# Analog_Teil_-_Kopie.net
KiCad netlist of a schematic drawn in EAGLE
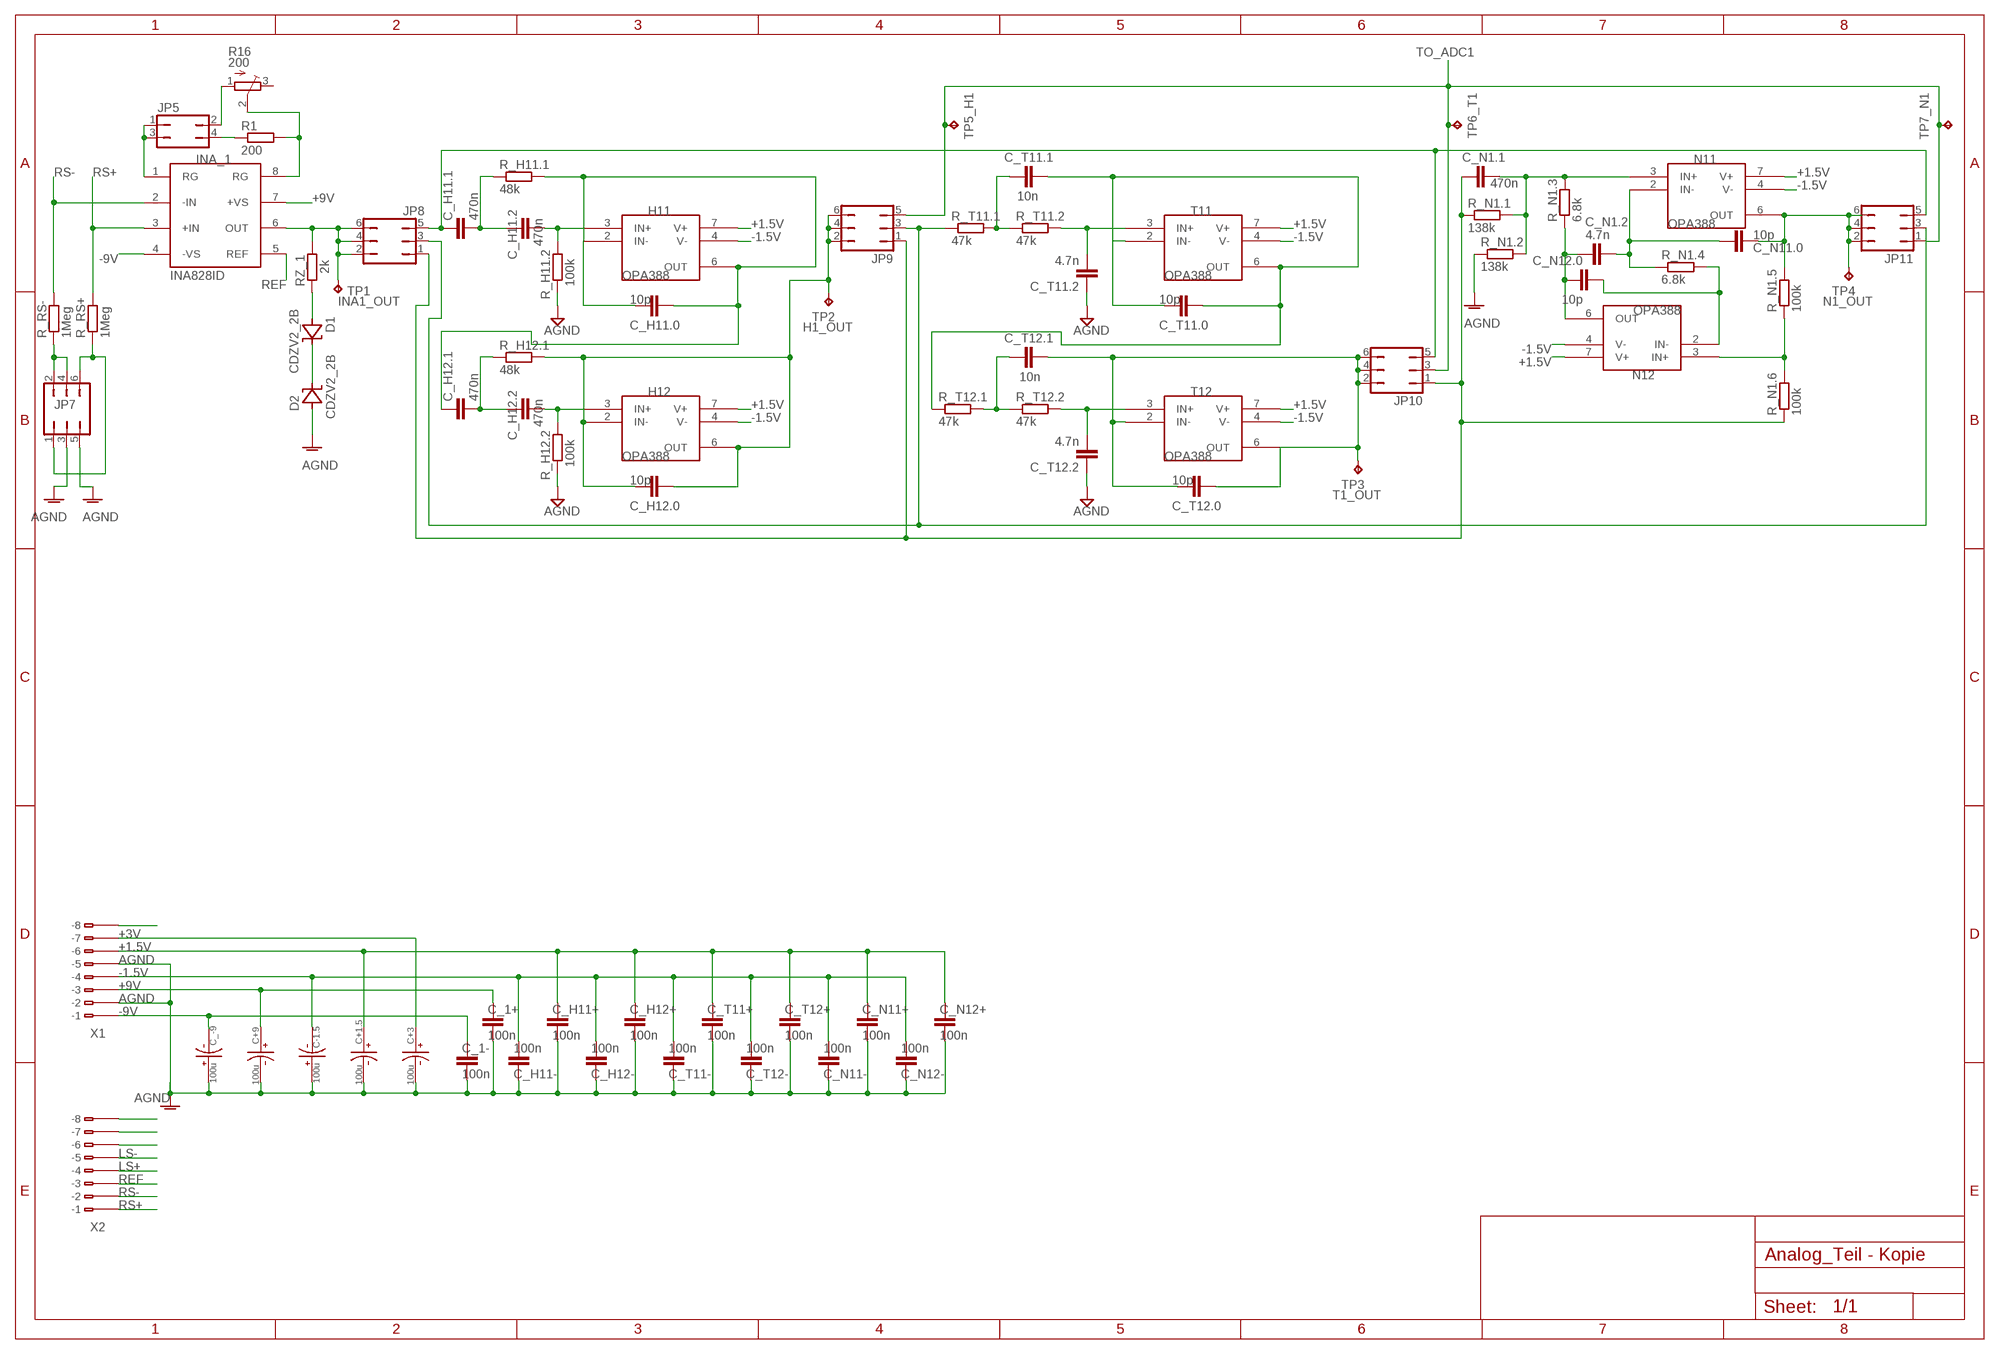
[diagram p0: schematic, sheet 1]

(export (version "E")
  (design (tool "Eeschema 10.0.6"))
  (components
    (comp (ref "C+1.5")
      (value "100u")
      (footprint "eagle-import:CAPPRD350W60D800H1150B")
      (fields (field (name "MF") "Panasonic Electronic") (field (name "MP") "ECA1HM101"))
      (libsource (lib "eagle-import") (part "ECA-1HM101"))
    )
    (comp (ref "C+3")
      (value "100u")
      (footprint "eagle-import:CAPPRD350W60D800H1150B")
      (fields (field (name "MF") "Panasonic Electronic") (field (name "MP") "ECA1HM101"))
      (libsource (lib "eagle-import") (part "ECA-1HM101"))
    )
    (comp (ref "C+9")
      (value "100u")
      (footprint "eagle-import:CAPPRD350W60D800H1150B")
      (fields (field (name "MF") "Panasonic Electronic") (field (name "MP") "ECA1HM101"))
      (libsource (lib "eagle-import") (part "ECA-1HM101"))
    )
    (comp (ref "C-1.5")
      (value "100u")
      (footprint "eagle-import:CAPPRD350W60D800H1150B")
      (fields (field (name "MF") "Panasonic Electronic") (field (name "MP") "ECA1HM101"))
      (libsource (lib "eagle-import") (part "ECA-1HM101"))
    )
    (comp (ref "C_-9")
      (value "100u")
      (footprint "eagle-import:CAPPRD350W60D800H1150B")
      (fields (field (name "MF") "Panasonic Electronic") (field (name "MP") "ECA1HM101"))
      (libsource (lib "eagle-import") (part "ECA-1HM101"))
    )
    (comp (ref "C_1+")
      (value "100n")
      (footprint "eagle-import:C0805")
      (libsource (lib "eagle-import") (part "C-EUC0805"))
    )
    (comp (ref "C_1-")
      (value "100n")
      (footprint "eagle-import:C0805")
      (libsource (lib "eagle-import") (part "C-EUC0805"))
    )
    (comp (ref "C_H11+")
      (value "100n")
      (footprint "eagle-import:C0805")
      (libsource (lib "eagle-import") (part "C-EUC0805"))
    )
    (comp (ref "C_H11-")
      (value "100n")
      (footprint "eagle-import:C0805")
      (libsource (lib "eagle-import") (part "C-EUC0805"))
    )
    (comp (ref "C_H11.0")
      (value "10p")
      (footprint "eagle-import:C0805")
      (libsource (lib "eagle-import") (part "C-EUC0805"))
    )
    (comp (ref "C_H11.1")
      (value "470n")
      (footprint "eagle-import:C0805")
      (libsource (lib "eagle-import") (part "C-EUC0805"))
    )
    (comp (ref "C_H11.2")
      (value "470n")
      (footprint "eagle-import:C0805")
      (libsource (lib "eagle-import") (part "C-EUC0805"))
    )
    (comp (ref "C_H12+")
      (value "100n")
      (footprint "eagle-import:C0805")
      (libsource (lib "eagle-import") (part "C-EUC0805"))
    )
    (comp (ref "C_H12-")
      (value "100n")
      (footprint "eagle-import:C0805")
      (libsource (lib "eagle-import") (part "C-EUC0805"))
    )
    (comp (ref "C_H12.0")
      (value "10p")
      (footprint "eagle-import:C0805")
      (libsource (lib "eagle-import") (part "C-EUC0805"))
    )
    (comp (ref "C_H12.1")
      (value "470n")
      (footprint "eagle-import:C0805")
      (libsource (lib "eagle-import") (part "C-EUC0805"))
    )
    (comp (ref "C_H12.2")
      (value "470n")
      (footprint "eagle-import:C0805")
      (libsource (lib "eagle-import") (part "C-EUC0805"))
    )
    (comp (ref "C_N1.1")
      (value "470n")
      (footprint "eagle-import:C0805")
      (libsource (lib "eagle-import") (part "C-EUC0805"))
    )
    (comp (ref "C_N1.2")
      (value "4.7n")
      (footprint "eagle-import:C0805")
      (libsource (lib "eagle-import") (part "C-EUC0805"))
    )
    (comp (ref "C_N11+")
      (value "100n")
      (footprint "eagle-import:C0805")
      (libsource (lib "eagle-import") (part "C-EUC0805"))
    )
    (comp (ref "C_N11-")
      (value "100n")
      (footprint "eagle-import:C0805")
      (libsource (lib "eagle-import") (part "C-EUC0805"))
    )
    (comp (ref "C_N11.0")
      (value "10p")
      (footprint "eagle-import:C0805")
      (libsource (lib "eagle-import") (part "C-EUC0805"))
    )
    (comp (ref "C_N12+")
      (value "100n")
      (footprint "eagle-import:C0805")
      (libsource (lib "eagle-import") (part "C-EUC0805"))
    )
    (comp (ref "C_N12-")
      (value "100n")
      (footprint "eagle-import:C0805")
      (libsource (lib "eagle-import") (part "C-EUC0805"))
    )
    (comp (ref "C_N12.0")
      (value "10p")
      (footprint "eagle-import:C0805")
      (libsource (lib "eagle-import") (part "C-EUC0805"))
    )
    (comp (ref "C_T11+")
      (value "100n")
      (footprint "eagle-import:C0805")
      (libsource (lib "eagle-import") (part "C-EUC0805"))
    )
    (comp (ref "C_T11-")
      (value "100n")
      (footprint "eagle-import:C0805")
      (libsource (lib "eagle-import") (part "C-EUC0805"))
    )
    (comp (ref "C_T11.0")
      (value "10p")
      (footprint "eagle-import:C0805")
      (libsource (lib "eagle-import") (part "C-EUC0805"))
    )
    (comp (ref "C_T11.1")
      (value "10n")
      (footprint "eagle-import:C0805")
      (libsource (lib "eagle-import") (part "C-EUC0805"))
    )
    (comp (ref "C_T11.2")
      (value "4.7n")
      (footprint "eagle-import:C0805")
      (libsource (lib "eagle-import") (part "C-EUC0805"))
    )
    (comp (ref "C_T12+")
      (value "100n")
      (footprint "eagle-import:C0805")
      (libsource (lib "eagle-import") (part "C-EUC0805"))
    )
    (comp (ref "C_T12-")
      (value "100n")
      (footprint "eagle-import:C0805")
      (libsource (lib "eagle-import") (part "C-EUC0805"))
    )
    (comp (ref "C_T12.0")
      (value "10p")
      (footprint "eagle-import:C0805")
      (libsource (lib "eagle-import") (part "C-EUC0805"))
    )
    (comp (ref "C_T12.1")
      (value "10n")
      (footprint "eagle-import:C0805")
      (libsource (lib "eagle-import") (part "C-EUC0805"))
    )
    (comp (ref "C_T12.2")
      (value "4.7n")
      (footprint "eagle-import:C0805")
      (libsource (lib "eagle-import") (part "C-EUC0805"))
    )
    (comp (ref "D1")
      (value "CDZV2_2B")
      (footprint "eagle-import:SODFL1006X40N")
      (libsource (lib "eagle-import") (part "CDZV2_2BSOD923"))
    )
    (comp (ref "D2")
      (value "CDZV2_2B")
      (footprint "eagle-import:SODFL1006X40N")
      (libsource (lib "eagle-import") (part "CDZV2_2BSOD923"))
    )
    (comp (ref "H11")
      (value "OPA388")
      (footprint "eagle-import:SOIC127P600X175-8N")
      (libsource (lib "eagle-import") (part "OPA388"))
    )
    (comp (ref "H12")
      (value "OPA388")
      (footprint "eagle-import:SOIC127P600X175-8N")
      (libsource (lib "eagle-import") (part "OPA388"))
    )
    (comp (ref "INA_1")
      (value "INA828ID")
      (footprint "eagle-import:SOIC8")
      (fields (field (name "DIGI-KEY_PART_NUMBER") "296-47415-ND") (field (name "MF") "Texas Instruments"))
      (libsource (lib "eagle-import") (part "INA828ID"))
    )
    (comp (ref "JP5")
      (value "JP2Q")
      (footprint "eagle-import:JP2Q")
      (libsource (lib "eagle-import") (part "JP2Q"))
    )
    (comp (ref "JP7")
      (value "JP3Q")
      (footprint "eagle-import:JP3Q")
      (libsource (lib "eagle-import") (part "JP3Q"))
    )
    (comp (ref "JP8")
      (value "JP3Q")
      (footprint "eagle-import:JP3Q")
      (libsource (lib "eagle-import") (part "JP3Q"))
    )
    (comp (ref "JP9")
      (value "JP3Q")
      (footprint "eagle-import:JP3Q")
      (libsource (lib "eagle-import") (part "JP3Q"))
    )
    (comp (ref "JP10")
      (value "JP3Q")
      (footprint "eagle-import:JP3Q")
      (libsource (lib "eagle-import") (part "JP3Q"))
    )
    (comp (ref "JP11")
      (value "JP3Q")
      (footprint "eagle-import:JP3Q")
      (libsource (lib "eagle-import") (part "JP3Q"))
    )
    (comp (ref "N11")
      (value "OPA388")
      (footprint "eagle-import:SOIC127P600X175-8N")
      (libsource (lib "eagle-import") (part "OPA388"))
    )
    (comp (ref "N12")
      (value "OPA388")
      (footprint "eagle-import:SOIC127P600X175-8N")
      (libsource (lib "eagle-import") (part "OPA388"))
    )
    (comp (ref "R1")
      (value "200")
      (footprint "eagle-import:R0805")
      (libsource (lib "eagle-import") (part "R-EU_R0805"))
    )
    (comp (ref "R16")
      (value "200")
      (footprint "eagle-import:SM-42_43W")
      (fields (field (name "SPICEPREFIX") "J"))
      (libsource (lib "eagle-import") (part "TRIM_EU-SM-42/43W"))
    )
    (comp (ref "RZ_1")
      (value "2k")
      (footprint "eagle-import:R0805")
      (libsource (lib "eagle-import") (part "R-EU_R0805"))
    )
    (comp (ref "R_H11.1")
      (value "48k")
      (footprint "eagle-import:R0805")
      (libsource (lib "eagle-import") (part "R-EU_R0805"))
    )
    (comp (ref "R_H11.2")
      (value "100k")
      (footprint "eagle-import:R0805")
      (libsource (lib "eagle-import") (part "R-EU_R0805"))
    )
    (comp (ref "R_H12.1")
      (value "48k")
      (footprint "eagle-import:R0805")
      (libsource (lib "eagle-import") (part "R-EU_R0805"))
    )
    (comp (ref "R_H12.2")
      (value "100k")
      (footprint "eagle-import:R0805")
      (libsource (lib "eagle-import") (part "R-EU_R0805"))
    )
    (comp (ref "R_N1.1")
      (value "138k")
      (footprint "eagle-import:R0805")
      (libsource (lib "eagle-import") (part "R-EU_R0805"))
    )
    (comp (ref "R_N1.2")
      (value "138k")
      (footprint "eagle-import:R0805")
      (libsource (lib "eagle-import") (part "R-EU_R0805"))
    )
    (comp (ref "R_N1.3")
      (value "6.8k")
      (footprint "eagle-import:R0805")
      (libsource (lib "eagle-import") (part "R-EU_R0805"))
    )
    (comp (ref "R_N1.4")
      (value "6.8k")
      (footprint "eagle-import:R0805")
      (libsource (lib "eagle-import") (part "R-EU_R0805"))
    )
    (comp (ref "R_N1.5")
      (value "100k")
      (footprint "eagle-import:R0805")
      (libsource (lib "eagle-import") (part "R-EU_R0805"))
    )
    (comp (ref "R_N1.6")
      (value "100k")
      (footprint "eagle-import:R0805")
      (libsource (lib "eagle-import") (part "R-EU_R0805"))
    )
    (comp (ref "R_RS+")
      (value "1Meg")
      (footprint "eagle-import:R0805")
      (libsource (lib "eagle-import") (part "R-EU_R0805"))
    )
    (comp (ref "R_RS-")
      (value "1Meg")
      (footprint "eagle-import:R0805")
      (libsource (lib "eagle-import") (part "R-EU_R0805"))
    )
    (comp (ref "R_T11.1")
      (value "47k")
      (footprint "eagle-import:R0805")
      (libsource (lib "eagle-import") (part "R-EU_R0805"))
    )
    (comp (ref "R_T11.2")
      (value "47k")
      (footprint "eagle-import:R0805")
      (libsource (lib "eagle-import") (part "R-EU_R0805"))
    )
    (comp (ref "R_T12.1")
      (value "47k")
      (footprint "eagle-import:R0805")
      (libsource (lib "eagle-import") (part "R-EU_R0805"))
    )
    (comp (ref "R_T12.2")
      (value "47k")
      (footprint "eagle-import:R0805")
      (libsource (lib "eagle-import") (part "R-EU_R0805"))
    )
    (comp (ref "T11")
      (value "OPA388")
      (footprint "eagle-import:SOIC127P600X175-8N")
      (libsource (lib "eagle-import") (part "OPA388"))
    )
    (comp (ref "T12")
      (value "OPA388")
      (footprint "eagle-import:SOIC127P600X175-8N")
      (libsource (lib "eagle-import") (part "OPA388"))
    )
    (comp (ref "TP1")
      (value "TPPAD1-13")
      (footprint "eagle-import:P1-13")
      (libsource (lib "eagle-import") (part "TPPAD1-13"))
    )
    (comp (ref "TP2")
      (value "TPPAD1-13")
      (footprint "eagle-import:P1-13")
      (libsource (lib "eagle-import") (part "TPPAD1-13"))
    )
    (comp (ref "TP3")
      (value "TPPAD1-13")
      (footprint "eagle-import:P1-13")
      (libsource (lib "eagle-import") (part "TPPAD1-13"))
    )
    (comp (ref "TP4")
      (value "TPPAD1-13")
      (footprint "eagle-import:P1-13")
      (libsource (lib "eagle-import") (part "TPPAD1-13"))
    )
    (comp (ref "TP5_H1")
      (value "TPPAD1-13")
      (footprint "eagle-import:P1-13")
      (libsource (lib "eagle-import") (part "TPPAD1-13"))
    )
    (comp (ref "TP6_T1")
      (value "TPPAD1-13")
      (footprint "eagle-import:P1-13")
      (libsource (lib "eagle-import") (part "TPPAD1-13"))
    )
    (comp (ref "TP7_N1")
      (value "TPPAD1-13")
      (footprint "eagle-import:P1-13")
      (libsource (lib "eagle-import") (part "TPPAD1-13"))
    )
    (comp (ref "X1")
      (value "233-108")
      (footprint "eagle-import:233-108")
      (libsource (lib "eagle-import") (part "233-108"))
    )
    (comp (ref "X2")
      (value "233-108")
      (footprint "eagle-import:233-108")
      (libsource (lib "eagle-import") (part "233-108"))
    )
  )
  (nets
    (net (code "1") (name "/+1.5V") (class "Default")
      (node (ref "C+1.5") (pin "+") (pinfunction "+_+") (pintype "passive"))
      (node (ref "C_H11+") (pin "1") (pinfunction "1_1") (pintype "passive"))
      (node (ref "C_H12+") (pin "1") (pinfunction "1_1") (pintype "passive"))
      (node (ref "C_N11+") (pin "1") (pinfunction "1_1") (pintype "passive"))
      (node (ref "C_N12+") (pin "1") (pinfunction "1_1") (pintype "passive"))
      (node (ref "C_T11+") (pin "1") (pinfunction "1_1") (pintype "passive"))
      (node (ref "C_T12+") (pin "1") (pinfunction "1_1") (pintype "passive"))
      (node (ref "H11") (pin "7") (pinfunction "V+_7") (pintype "power_in"))
      (node (ref "H12") (pin "7") (pinfunction "V+_7") (pintype "power_in"))
      (node (ref "N11") (pin "7") (pinfunction "V+_7") (pintype "power_in"))
      (node (ref "N12") (pin "7") (pinfunction "V+_7") (pintype "power_in"))
      (node (ref "T11") (pin "7") (pinfunction "V+_7") (pintype "power_in"))
      (node (ref "T12") (pin "7") (pinfunction "V+_7") (pintype "power_in"))
      (node (ref "X1") (pin "B6") (pinfunction "B-6_B6") (pintype "passive"))
    )
    (net (code "2") (name "/+3V") (class "Default")
      (node (ref "C+3") (pin "+") (pinfunction "+_+") (pintype "passive"))
      (node (ref "X1") (pin "B7") (pinfunction "B-7_B7") (pintype "passive"))
    )
    (net (code "3") (name "/+9V") (class "Default")
      (node (ref "C+9") (pin "+") (pinfunction "+_+") (pintype "passive"))
      (node (ref "C_1+") (pin "1") (pinfunction "1_1") (pintype "passive"))
      (node (ref "INA_1") (pin "7") (pinfunction "+VS_7") (pintype "bidirectional"))
      (node (ref "X1") (pin "B3") (pinfunction "B-3_B3") (pintype "passive"))
    )
    (net (code "4") (name "/-1.5V") (class "Default")
      (node (ref "C-1.5") (pin "-") (pinfunction "-_-") (pintype "passive"))
      (node (ref "C_H11-") (pin "2") (pinfunction "2_2") (pintype "passive"))
      (node (ref "C_H12-") (pin "2") (pinfunction "2_2") (pintype "passive"))
      (node (ref "C_N11-") (pin "2") (pinfunction "2_2") (pintype "passive"))
      (node (ref "C_N12-") (pin "2") (pinfunction "2_2") (pintype "passive"))
      (node (ref "C_T11-") (pin "2") (pinfunction "2_2") (pintype "passive"))
      (node (ref "C_T12-") (pin "2") (pinfunction "2_2") (pintype "passive"))
      (node (ref "H11") (pin "4") (pinfunction "V-_4") (pintype "power_in"))
      (node (ref "H12") (pin "4") (pinfunction "V-_4") (pintype "power_in"))
      (node (ref "N11") (pin "4") (pinfunction "V-_4") (pintype "power_in"))
      (node (ref "N12") (pin "4") (pinfunction "V-_4") (pintype "power_in"))
      (node (ref "T11") (pin "4") (pinfunction "V-_4") (pintype "power_in"))
      (node (ref "T12") (pin "4") (pinfunction "V-_4") (pintype "power_in"))
      (node (ref "X1") (pin "B4") (pinfunction "B-4_B4") (pintype "passive"))
    )
    (net (code "5") (name "/-9V") (class "Default")
      (node (ref "C_-9") (pin "-") (pinfunction "-_-") (pintype "passive"))
      (node (ref "C_1-") (pin "1") (pinfunction "1_1") (pintype "passive"))
      (node (ref "INA_1") (pin "4") (pinfunction "-VS_4") (pintype "bidirectional"))
      (node (ref "X1") (pin "B1") (pinfunction "B-1_B1") (pintype "passive"))
    )
    (net (code "6") (name "/H1_OUT") (class "Default")
      (node (ref "C_H12.0") (pin "1") (pinfunction "1_1") (pintype "passive"))
      (node (ref "C_H12.0") (pin "2") (pinfunction "2_2") (pintype "passive"))
      (node (ref "H12") (pin "2") (pinfunction "IN-_2") (pintype "input"))
      (node (ref "H12") (pin "6") (pinfunction "OUT_6") (pintype "output"))
      (node (ref "JP9") (pin "2") (pinfunction "2_2") (pintype "passive"))
      (node (ref "JP9") (pin "4") (pinfunction "4_4") (pintype "passive"))
      (node (ref "JP9") (pin "6") (pinfunction "6_6") (pintype "passive"))
      (node (ref "R_H12.1") (pin "2") (pinfunction "2_2") (pintype "passive"))
      (node (ref "TP2") (pin "TP") (pinfunction "TP_TP") (pintype "input"))
    )
    (net (code "7") (name "/INA1_OUT") (class "Default")
      (node (ref "INA_1") (pin "6") (pinfunction "OUT_6") (pintype "bidirectional"))
      (node (ref "JP8") (pin "2") (pinfunction "2_2") (pintype "passive"))
      (node (ref "JP8") (pin "4") (pinfunction "4_4") (pintype "passive"))
      (node (ref "JP8") (pin "6") (pinfunction "6_6") (pintype "passive"))
      (node (ref "RZ_1") (pin "2") (pinfunction "2_2") (pintype "passive"))
      (node (ref "TP1") (pin "TP") (pinfunction "TP_TP") (pintype "input"))
    )
    (net (code "8") (name "/LS+") (class "Default")
      (node (ref "X2") (pin "B4") (pinfunction "B-4_B4") (pintype "passive"))
    )
    (net (code "9") (name "/LS-") (class "Default")
      (node (ref "X2") (pin "B5") (pinfunction "B-5_B5") (pintype "passive"))
    )
    (net (code "10") (name "/N1_OUT") (class "Default")
      (node (ref "C_N11.0") (pin "1") (pinfunction "1_1") (pintype "passive"))
      (node (ref "JP11") (pin "2") (pinfunction "2_2") (pintype "passive"))
      (node (ref "JP11") (pin "4") (pinfunction "4_4") (pintype "passive"))
      (node (ref "JP11") (pin "6") (pinfunction "6_6") (pintype "passive"))
      (node (ref "N11") (pin "6") (pinfunction "OUT_6") (pintype "output"))
      (node (ref "R_N1.5") (pin "2") (pinfunction "2_2") (pintype "passive"))
      (node (ref "TP4") (pin "TP") (pinfunction "TP_TP") (pintype "input"))
    )
    (net (code "11") (name "/REF") (class "Default")
      (node (ref "INA_1") (pin "5") (pinfunction "REF_5") (pintype "bidirectional"))
      (node (ref "X2") (pin "B3") (pinfunction "B-3_B3") (pintype "passive"))
    )
    (net (code "12") (name "/RS+") (class "Default")
      (node (ref "INA_1") (pin "3") (pinfunction "+IN_3") (pintype "bidirectional"))
      (node (ref "R_RS+") (pin "2") (pinfunction "2_2") (pintype "passive"))
      (node (ref "X2") (pin "B1") (pinfunction "B-1_B1") (pintype "passive"))
    )
    (net (code "13") (name "/RS-") (class "Default")
      (node (ref "INA_1") (pin "2") (pinfunction "-IN_2") (pintype "bidirectional"))
      (node (ref "R_RS-") (pin "2") (pinfunction "2_2") (pintype "passive"))
      (node (ref "X2") (pin "B2") (pinfunction "B-2_B2") (pintype "passive"))
    )
    (net (code "14") (name "/T1_OUT") (class "Default")
      (node (ref "C_T12.0") (pin "1") (pinfunction "1_1") (pintype "passive"))
      (node (ref "C_T12.0") (pin "2") (pinfunction "2_2") (pintype "passive"))
      (node (ref "C_T12.1") (pin "2") (pinfunction "2_2") (pintype "passive"))
      (node (ref "JP10") (pin "2") (pinfunction "2_2") (pintype "passive"))
      (node (ref "JP10") (pin "4") (pinfunction "4_4") (pintype "passive"))
      (node (ref "JP10") (pin "6") (pinfunction "6_6") (pintype "passive"))
      (node (ref "T12") (pin "2") (pinfunction "IN-_2") (pintype "input"))
      (node (ref "T12") (pin "6") (pinfunction "OUT_6") (pintype "output"))
      (node (ref "TP3") (pin "TP") (pinfunction "TP_TP") (pintype "input"))
    )
    (net (code "15") (name "/TO_ADC1") (class "Default")
      (node (ref "JP10") (pin "3") (pinfunction "3_3") (pintype "passive"))
      (node (ref "JP11") (pin "1") (pinfunction "1_1") (pintype "passive"))
      (node (ref "JP9") (pin "5") (pinfunction "5_5") (pintype "passive"))
      (node (ref "TP5_H1") (pin "TP") (pinfunction "TP_TP") (pintype "input"))
      (node (ref "TP6_T1") (pin "TP") (pinfunction "TP_TP") (pintype "input"))
      (node (ref "TP7_N1") (pin "TP") (pinfunction "TP_TP") (pintype "input"))
    )
    (net (code "16") (name "AGND") (class "Default")
      (node (ref "C+1.5") (pin "-") (pinfunction "-_-") (pintype "passive"))
      (node (ref "C+3") (pin "-") (pinfunction "-_-") (pintype "passive"))
      (node (ref "C+9") (pin "-") (pinfunction "-_-") (pintype "passive"))
      (node (ref "C-1.5") (pin "+") (pinfunction "+_+") (pintype "passive"))
      (node (ref "C_-9") (pin "+") (pinfunction "+_+") (pintype "passive"))
      (node (ref "C_1+") (pin "2") (pinfunction "2_2") (pintype "passive"))
      (node (ref "C_1-") (pin "2") (pinfunction "2_2") (pintype "passive"))
      (node (ref "C_H11+") (pin "2") (pinfunction "2_2") (pintype "passive"))
      (node (ref "C_H11-") (pin "1") (pinfunction "1_1") (pintype "passive"))
      (node (ref "C_H12+") (pin "2") (pinfunction "2_2") (pintype "passive"))
      (node (ref "C_H12-") (pin "1") (pinfunction "1_1") (pintype "passive"))
      (node (ref "C_N11+") (pin "2") (pinfunction "2_2") (pintype "passive"))
      (node (ref "C_N11-") (pin "1") (pinfunction "1_1") (pintype "passive"))
      (node (ref "C_N12+") (pin "2") (pinfunction "2_2") (pintype "passive"))
      (node (ref "C_N12-") (pin "1") (pinfunction "1_1") (pintype "passive"))
      (node (ref "C_T11+") (pin "2") (pinfunction "2_2") (pintype "passive"))
      (node (ref "C_T11-") (pin "1") (pinfunction "1_1") (pintype "passive"))
      (node (ref "C_T11.2") (pin "1") (pinfunction "1_1") (pintype "passive"))
      (node (ref "C_T12+") (pin "2") (pinfunction "2_2") (pintype "passive"))
      (node (ref "C_T12-") (pin "1") (pinfunction "1_1") (pintype "passive"))
      (node (ref "C_T12.2") (pin "1") (pinfunction "1_1") (pintype "passive"))
      (node (ref "D2") (pin "1") (pinfunction "A_1") (pintype "passive"))
      (node (ref "JP7") (pin "3") (pinfunction "3_3") (pintype "passive"))
      (node (ref "JP7") (pin "5") (pinfunction "5_5") (pintype "passive"))
      (node (ref "R_H11.2") (pin "1") (pinfunction "1_1") (pintype "passive"))
      (node (ref "R_H12.2") (pin "1") (pinfunction "1_1") (pintype "passive"))
      (node (ref "R_N1.2") (pin "1") (pinfunction "1_1") (pintype "passive"))
      (node (ref "X1") (pin "B2") (pinfunction "B-2_B2") (pintype "passive"))
      (node (ref "X1") (pin "B5") (pinfunction "B-5_B5") (pintype "passive"))
    )
    (net (code "17") (name "Net-(C_H11.1-Pad1)") (class "Default")
      (node (ref "C_H11.1") (pin "1") (pinfunction "1_1") (pintype "passive"))
      (node (ref "JP10") (pin "5") (pinfunction "5_5") (pintype "passive"))
      (node (ref "JP11") (pin "5") (pinfunction "5_5") (pintype "passive"))
      (node (ref "JP8") (pin "5") (pinfunction "5_5") (pintype "passive"))
    )
    (net (code "18") (name "Net-(C_H11.1-Pad2)") (class "Default")
      (node (ref "C_H11.1") (pin "2") (pinfunction "2_2") (pintype "passive"))
      (node (ref "C_H11.2") (pin "1") (pinfunction "1_1") (pintype "passive"))
      (node (ref "R_H11.1") (pin "1") (pinfunction "1_1") (pintype "passive"))
    )
    (net (code "19") (name "Net-(C_H12.1-Pad2)") (class "Default")
      (node (ref "C_H12.1") (pin "2") (pinfunction "2_2") (pintype "passive"))
      (node (ref "C_H12.2") (pin "1") (pinfunction "1_1") (pintype "passive"))
      (node (ref "R_H12.1") (pin "1") (pinfunction "1_1") (pintype "passive"))
    )
    (net (code "20") (name "Net-(C_N1.1-Pad1)") (class "Default")
      (node (ref "C_N1.1") (pin "1") (pinfunction "1_1") (pintype "passive"))
      (node (ref "JP10") (pin "1") (pinfunction "1_1") (pintype "passive"))
      (node (ref "JP8") (pin "1") (pinfunction "1_1") (pintype "passive"))
      (node (ref "JP9") (pin "1") (pinfunction "1_1") (pintype "passive"))
      (node (ref "R_N1.1") (pin "1") (pinfunction "1_1") (pintype "passive"))
      (node (ref "R_N1.6") (pin "1") (pinfunction "1_1") (pintype "passive"))
    )
    (net (code "21") (name "Net-(C_T11.1-Pad1)") (class "Default")
      (node (ref "C_T11.1") (pin "1") (pinfunction "1_1") (pintype "passive"))
      (node (ref "R_T11.1") (pin "2") (pinfunction "2_2") (pintype "passive"))
      (node (ref "R_T11.2") (pin "1") (pinfunction "1_1") (pintype "passive"))
    )
    (net (code "22") (name "Net-(C_T12.1-Pad1)") (class "Default")
      (node (ref "C_T12.1") (pin "1") (pinfunction "1_1") (pintype "passive"))
      (node (ref "R_T12.1") (pin "2") (pinfunction "2_2") (pintype "passive"))
      (node (ref "R_T12.2") (pin "1") (pinfunction "1_1") (pintype "passive"))
    )
    (net (code "23") (name "Net-(D1-A)") (class "Default")
      (node (ref "D1") (pin "1") (pinfunction "A_1") (pintype "passive"))
      (node (ref "RZ_1") (pin "1") (pinfunction "1_1") (pintype "passive"))
    )
    (net (code "24") (name "Net-(D1-C)") (class "Default")
      (node (ref "D1") (pin "2") (pinfunction "C_2") (pintype "passive"))
      (node (ref "D2") (pin "2") (pinfunction "C_2") (pintype "passive"))
    )
    (net (code "25") (name "Net-(H11-IN+)") (class "Default")
      (node (ref "C_H11.2") (pin "2") (pinfunction "2_2") (pintype "passive"))
      (node (ref "H11") (pin "3") (pinfunction "IN+_3") (pintype "input"))
      (node (ref "R_H11.2") (pin "2") (pinfunction "2_2") (pintype "passive"))
    )
    (net (code "26") (name "Net-(H11-IN-)") (class "Default")
      (node (ref "C_H11.0") (pin "1") (pinfunction "1_1") (pintype "passive"))
      (node (ref "C_H11.0") (pin "2") (pinfunction "2_2") (pintype "passive"))
      (node (ref "C_H12.1") (pin "1") (pinfunction "1_1") (pintype "passive"))
      (node (ref "H11") (pin "2") (pinfunction "IN-_2") (pintype "input"))
      (node (ref "H11") (pin "6") (pinfunction "OUT_6") (pintype "output"))
      (node (ref "R_H11.1") (pin "2") (pinfunction "2_2") (pintype "passive"))
    )
    (net (code "27") (name "Net-(H12-IN+)") (class "Default")
      (node (ref "C_H12.2") (pin "2") (pinfunction "2_2") (pintype "passive"))
      (node (ref "H12") (pin "3") (pinfunction "IN+_3") (pintype "input"))
      (node (ref "R_H12.2") (pin "2") (pinfunction "2_2") (pintype "passive"))
    )
    (net (code "28") (name "Net-(INA_1-RG-Pad1)") (class "Default")
      (node (ref "INA_1") (pin "1") (pinfunction "RG_1") (pintype "bidirectional"))
      (node (ref "JP5") (pin "1") (pinfunction "1_1") (pintype "passive"))
      (node (ref "JP5") (pin "3") (pinfunction "3_3") (pintype "passive"))
    )
    (net (code "29") (name "Net-(JP5-Pad4)") (class "Default")
      (node (ref "JP5") (pin "4") (pinfunction "4_4") (pintype "passive"))
      (node (ref "R1") (pin "1") (pinfunction "1_1") (pintype "passive"))
    )
    (net (code "30") (name "Net-(JP7-Pad1)") (class "Default")
      (node (ref "JP7") (pin "1") (pinfunction "1_1") (pintype "passive"))
      (node (ref "JP7") (pin "6") (pinfunction "6_6") (pintype "passive"))
      (node (ref "R_RS+") (pin "1") (pinfunction "1_1") (pintype "passive"))
    )
    (net (code "31") (name "Net-(JP7-Pad2)") (class "Default")
      (node (ref "JP7") (pin "2") (pinfunction "2_2") (pintype "passive"))
      (node (ref "JP7") (pin "4") (pinfunction "4_4") (pintype "passive"))
      (node (ref "R_RS-") (pin "1") (pinfunction "1_1") (pintype "passive"))
    )
    (net (code "32") (name "Net-(JP11-Pad3)") (class "Default")
      (node (ref "JP11") (pin "3") (pinfunction "3_3") (pintype "passive"))
      (node (ref "JP8") (pin "3") (pinfunction "3_3") (pintype "passive"))
      (node (ref "JP9") (pin "3") (pinfunction "3_3") (pintype "passive"))
      (node (ref "R_T11.1") (pin "1") (pinfunction "1_1") (pintype "passive"))
    )
    (net (code "33") (name "Net-(N11-IN+)") (class "Default")
      (node (ref "C_N1.1") (pin "2") (pinfunction "2_2") (pintype "passive"))
      (node (ref "N11") (pin "3") (pinfunction "IN+_3") (pintype "input"))
      (node (ref "R_N1.1") (pin "2") (pinfunction "2_2") (pintype "passive"))
      (node (ref "R_N1.2") (pin "2") (pinfunction "2_2") (pintype "passive"))
      (node (ref "R_N1.3") (pin "2") (pinfunction "2_2") (pintype "passive"))
    )
    (net (code "34") (name "Net-(N11-IN-)") (class "Default")
      (node (ref "C_N1.2") (pin "2") (pinfunction "2_2") (pintype "passive"))
      (node (ref "C_N11.0") (pin "2") (pinfunction "2_2") (pintype "passive"))
      (node (ref "N11") (pin "2") (pinfunction "IN-_2") (pintype "input"))
      (node (ref "R_N1.4") (pin "1") (pinfunction "1_1") (pintype "passive"))
    )
    (net (code "35") (name "Net-(N12-IN+)") (class "Default")
      (node (ref "N12") (pin "3") (pinfunction "IN+_3") (pintype "input"))
      (node (ref "R_N1.5") (pin "1") (pinfunction "1_1") (pintype "passive"))
      (node (ref "R_N1.6") (pin "2") (pinfunction "2_2") (pintype "passive"))
    )
    (net (code "36") (name "Net-(N12-IN-)") (class "Default")
      (node (ref "C_N12.0") (pin "1") (pinfunction "1_1") (pintype "passive"))
      (node (ref "N12") (pin "2") (pinfunction "IN-_2") (pintype "input"))
      (node (ref "R_N1.4") (pin "2") (pinfunction "2_2") (pintype "passive"))
    )
    (net (code "37") (name "Net-(N12-OUT)") (class "Default")
      (node (ref "C_N1.2") (pin "1") (pinfunction "1_1") (pintype "passive"))
      (node (ref "C_N12.0") (pin "2") (pinfunction "2_2") (pintype "passive"))
      (node (ref "N12") (pin "6") (pinfunction "OUT_6") (pintype "output"))
      (node (ref "R_N1.3") (pin "1") (pinfunction "1_1") (pintype "passive"))
    )
    (net (code "38") (name "Net-(R16-A)") (class "Default")
      (node (ref "JP5") (pin "2") (pinfunction "2_2") (pintype "passive"))
      (node (ref "R16") (pin "1") (pinfunction "A_1") (pintype "passive"))
    )
    (net (code "39") (name "Net-(R16-S)") (class "Default")
      (node (ref "INA_1") (pin "8") (pinfunction "RG_8") (pintype "bidirectional"))
      (node (ref "R1") (pin "2") (pinfunction "2_2") (pintype "passive"))
      (node (ref "R16") (pin "2") (pinfunction "S_2") (pintype "passive"))
    )
    (net (code "40") (name "Net-(T11-IN+)") (class "Default")
      (node (ref "C_T11.2") (pin "2") (pinfunction "2_2") (pintype "passive"))
      (node (ref "R_T11.2") (pin "2") (pinfunction "2_2") (pintype "passive"))
      (node (ref "T11") (pin "3") (pinfunction "IN+_3") (pintype "input"))
    )
    (net (code "41") (name "Net-(T11-IN-)") (class "Default")
      (node (ref "C_T11.0") (pin "1") (pinfunction "1_1") (pintype "passive"))
      (node (ref "C_T11.0") (pin "2") (pinfunction "2_2") (pintype "passive"))
      (node (ref "C_T11.1") (pin "2") (pinfunction "2_2") (pintype "passive"))
      (node (ref "R_T12.1") (pin "1") (pinfunction "1_1") (pintype "passive"))
      (node (ref "T11") (pin "2") (pinfunction "IN-_2") (pintype "input"))
      (node (ref "T11") (pin "6") (pinfunction "OUT_6") (pintype "output"))
    )
    (net (code "42") (name "Net-(T12-IN+)") (class "Default")
      (node (ref "C_T12.2") (pin "2") (pinfunction "2_2") (pintype "passive"))
      (node (ref "R_T12.2") (pin "2") (pinfunction "2_2") (pintype "passive"))
      (node (ref "T12") (pin "3") (pinfunction "IN+_3") (pintype "input"))
    )
    (net (code "43") (name "unconnected-(H11-NC1-Pad1)") (class "Default")
      (node (ref "H11") (pin "1") (pinfunction "NC1_1") (pintype "no_connect"))
    )
    (net (code "44") (name "unconnected-(H11-NC2-Pad5)") (class "Default")
      (node (ref "H11") (pin "5") (pinfunction "NC2_5") (pintype "no_connect"))
    )
    (net (code "45") (name "unconnected-(H11-NC3-Pad8)") (class "Default")
      (node (ref "H11") (pin "8") (pinfunction "NC3_8") (pintype "no_connect"))
    )
    (net (code "46") (name "unconnected-(H12-NC1-Pad1)") (class "Default")
      (node (ref "H12") (pin "1") (pinfunction "NC1_1") (pintype "no_connect"))
    )
    (net (code "47") (name "unconnected-(H12-NC2-Pad5)") (class "Default")
      (node (ref "H12") (pin "5") (pinfunction "NC2_5") (pintype "no_connect"))
    )
    (net (code "48") (name "unconnected-(H12-NC3-Pad8)") (class "Default")
      (node (ref "H12") (pin "8") (pinfunction "NC3_8") (pintype "no_connect"))
    )
    (net (code "49") (name "unconnected-(N11-NC1-Pad1)") (class "Default")
      (node (ref "N11") (pin "1") (pinfunction "NC1_1") (pintype "no_connect"))
    )
    (net (code "50") (name "unconnected-(N11-NC2-Pad5)") (class "Default")
      (node (ref "N11") (pin "5") (pinfunction "NC2_5") (pintype "no_connect"))
    )
    (net (code "51") (name "unconnected-(N11-NC3-Pad8)") (class "Default")
      (node (ref "N11") (pin "8") (pinfunction "NC3_8") (pintype "no_connect"))
    )
    (net (code "52") (name "unconnected-(N12-NC1-Pad1)") (class "Default")
      (node (ref "N12") (pin "1") (pinfunction "NC1_1") (pintype "no_connect"))
    )
    (net (code "53") (name "unconnected-(N12-NC2-Pad5)") (class "Default")
      (node (ref "N12") (pin "5") (pinfunction "NC2_5") (pintype "no_connect"))
    )
    (net (code "54") (name "unconnected-(N12-NC3-Pad8)") (class "Default")
      (node (ref "N12") (pin "8") (pinfunction "NC3_8") (pintype "no_connect"))
    )
    (net (code "55") (name "unconnected-(R16-E-Pad3)") (class "Default")
      (node (ref "R16") (pin "3") (pinfunction "E_3") (pintype "passive"))
    )
    (net (code "56") (name "unconnected-(T11-NC1-Pad1)") (class "Default")
      (node (ref "T11") (pin "1") (pinfunction "NC1_1") (pintype "no_connect"))
    )
    (net (code "57") (name "unconnected-(T11-NC2-Pad5)") (class "Default")
      (node (ref "T11") (pin "5") (pinfunction "NC2_5") (pintype "no_connect"))
    )
    (net (code "58") (name "unconnected-(T11-NC3-Pad8)") (class "Default")
      (node (ref "T11") (pin "8") (pinfunction "NC3_8") (pintype "no_connect"))
    )
    (net (code "59") (name "unconnected-(T12-NC1-Pad1)") (class "Default")
      (node (ref "T12") (pin "1") (pinfunction "NC1_1") (pintype "no_connect"))
    )
    (net (code "60") (name "unconnected-(T12-NC2-Pad5)") (class "Default")
      (node (ref "T12") (pin "5") (pinfunction "NC2_5") (pintype "no_connect"))
    )
    (net (code "61") (name "unconnected-(T12-NC3-Pad8)") (class "Default")
      (node (ref "T12") (pin "8") (pinfunction "NC3_8") (pintype "no_connect"))
    )
    (net (code "62") (name "unconnected-(X1--1-PadA1)") (class "Default")
      (node (ref "X1") (pin "A1") (pinfunction "-1_A1") (pintype "passive"))
    )
    (net (code "63") (name "unconnected-(X1--2-PadA2)") (class "Default")
      (node (ref "X1") (pin "A2") (pinfunction "-2_A2") (pintype "passive"))
    )
    (net (code "64") (name "unconnected-(X1--3-PadA3)") (class "Default")
      (node (ref "X1") (pin "A3") (pinfunction "-3_A3") (pintype "passive"))
    )
    (net (code "65") (name "unconnected-(X1--4-PadA4)") (class "Default")
      (node (ref "X1") (pin "A4") (pinfunction "-4_A4") (pintype "passive"))
    )
    (net (code "66") (name "unconnected-(X1--5-PadA5)") (class "Default")
      (node (ref "X1") (pin "A5") (pinfunction "-5_A5") (pintype "passive"))
    )
    (net (code "67") (name "unconnected-(X1--6-PadA6)") (class "Default")
      (node (ref "X1") (pin "A6") (pinfunction "-6_A6") (pintype "passive"))
    )
    (net (code "68") (name "unconnected-(X1--7-PadA7)") (class "Default")
      (node (ref "X1") (pin "A7") (pinfunction "-7_A7") (pintype "passive"))
    )
    (net (code "69") (name "unconnected-(X1--8-PadA8)") (class "Default")
      (node (ref "X1") (pin "A8") (pinfunction "-8_A8") (pintype "passive"))
    )
    (net (code "70") (name "unconnected-(X1-B-8-PadB8)") (class "Default")
      (node (ref "X1") (pin "B8") (pinfunction "B-8_B8") (pintype "passive"))
    )
    (net (code "71") (name "unconnected-(X2--1-PadA1)") (class "Default")
      (node (ref "X2") (pin "A1") (pinfunction "-1_A1") (pintype "passive"))
    )
    (net (code "72") (name "unconnected-(X2--2-PadA2)") (class "Default")
      (node (ref "X2") (pin "A2") (pinfunction "-2_A2") (pintype "passive"))
    )
    (net (code "73") (name "unconnected-(X2--3-PadA3)") (class "Default")
      (node (ref "X2") (pin "A3") (pinfunction "-3_A3") (pintype "passive"))
    )
    (net (code "74") (name "unconnected-(X2--4-PadA4)") (class "Default")
      (node (ref "X2") (pin "A4") (pinfunction "-4_A4") (pintype "passive"))
    )
    (net (code "75") (name "unconnected-(X2--5-PadA5)") (class "Default")
      (node (ref "X2") (pin "A5") (pinfunction "-5_A5") (pintype "passive"))
    )
    (net (code "76") (name "unconnected-(X2--6-PadA6)") (class "Default")
      (node (ref "X2") (pin "A6") (pinfunction "-6_A6") (pintype "passive"))
    )
    (net (code "77") (name "unconnected-(X2--7-PadA7)") (class "Default")
      (node (ref "X2") (pin "A7") (pinfunction "-7_A7") (pintype "passive"))
    )
    (net (code "78") (name "unconnected-(X2--8-PadA8)") (class "Default")
      (node (ref "X2") (pin "A8") (pinfunction "-8_A8") (pintype "passive"))
    )
    (net (code "79") (name "unconnected-(X2-B-6-PadB6)") (class "Default")
      (node (ref "X2") (pin "B6") (pinfunction "B-6_B6") (pintype "passive"))
    )
    (net (code "80") (name "unconnected-(X2-B-7-PadB7)") (class "Default")
      (node (ref "X2") (pin "B7") (pinfunction "B-7_B7") (pintype "passive"))
    )
    (net (code "81") (name "unconnected-(X2-B-8-PadB8)") (class "Default")
      (node (ref "X2") (pin "B8") (pinfunction "B-8_B8") (pintype "passive"))
    )
  )
)
